# UART.net
KiCad netlist of a schematic drawn in Altium Designer
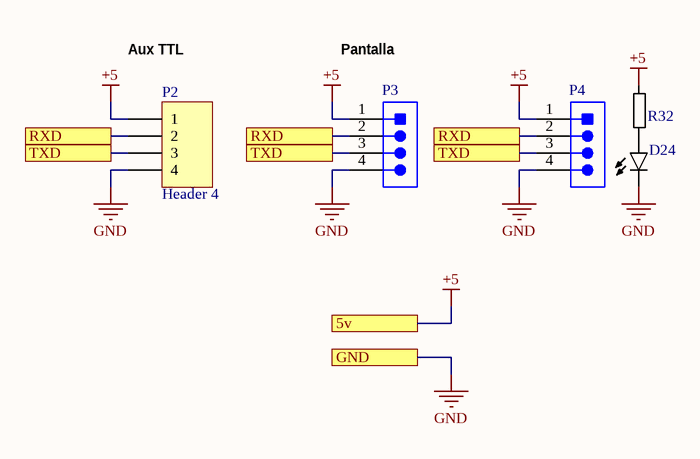
[diagram p0: UART.SchDoc]

(export (version "E")
  (design (tool "Eeschema 10.0.6"))
  (components
    (comp (ref "D24")
      (value "597-3305-607F")
      (footprint "0805 LED")
      (description "LED Uni-Color Green 4-Pin Chip 0805 T/R")
      (libsource (lib "597-3305-607F") (part "597-3305-607F"))
    )
    (comp (ref "P2")
      (value "Header 4")
      (footprint "HDR1X4")
      (description "Header, 4-Pin")
      (fields (field (name "PUBLISHER") "Altium Limited"))
      (libsource (lib "Miscellaneous Connectors") (part "Header 4"))
    )
    (comp (ref "P3")
      (value "B4B-PH-K-S(LF)(SN)")
      (footprint "JST-B4B-PH-K-S_V")
      (fields (field (name "MANUFACTURER") "JST"))
      (libsource (lib "Altium Content Vault") (part "CN-1P-M-R4"))
    )
    (comp (ref "P4")
      (value "B4B-PH-K-S(LF)(SN)")
      (footprint "JST-B4B-PH-K-S_V")
      (fields (field (name "MANUFACTURER") "JST"))
      (libsource (lib "Altium Content Vault") (part "CN-1P-M-R4"))
    )
    (comp (ref "R32")
      (value "CR0805-JW-221ELF")
      (footprint "0805 res")
      (description "220 Ohms Â±5% 0.125W, 1/8W Chip Resistor 0805 (2012 Metric) Moisture Resistant Thick Film")
      (fields (field (name "MF") "Bourns"))
      (libsource (lib "CR0805-JW-221ELF") (part "CR0805-JW-221ELF"))
    )
  )
  (nets
    (net (code "1") (name "+5") (class "Default")
      (node (ref "P2") (pin "1") (pinfunction "1_1") (pintype "passive"))
      (node (ref "P3") (pin "1") (pinfunction "1_1") (pintype "passive"))
      (node (ref "P4") (pin "1") (pinfunction "1_1") (pintype "passive"))
      (node (ref "R32") (pin "1") (pinfunction "1_1") (pintype "passive"))
    )
    (net (code "2") (name "/RXD") (class "Default")
      (node (ref "P2") (pin "2") (pinfunction "2_2") (pintype "passive"))
      (node (ref "P3") (pin "2") (pinfunction "2_2") (pintype "passive"))
      (node (ref "P4") (pin "2") (pinfunction "2_2") (pintype "passive"))
    )
    (net (code "3") (name "/TXD") (class "Default")
      (node (ref "P2") (pin "3") (pinfunction "3_3") (pintype "passive"))
      (node (ref "P3") (pin "3") (pinfunction "3_3") (pintype "passive"))
      (node (ref "P4") (pin "3") (pinfunction "3_3") (pintype "passive"))
    )
    (net (code "4") (name "GND") (class "Default")
      (node (ref "D24") (pin "C") (pinfunction "C_C") (pintype "passive"))
      (node (ref "P2") (pin "4") (pinfunction "4_4") (pintype "passive"))
      (node (ref "P3") (pin "4") (pinfunction "4_4") (pintype "passive"))
      (node (ref "P4") (pin "4") (pinfunction "4_4") (pintype "passive"))
    )
    (net (code "5") (name "Net-(D24-PadA)") (class "Default")
      (node (ref "D24") (pin "A") (pinfunction "A_A") (pintype "passive"))
      (node (ref "R32") (pin "2") (pinfunction "2_2") (pintype "passive"))
    )
  )
)
